# mainboard_interface_v1_2.net
KiCad netlist of a schematic drawn in Altium Designer
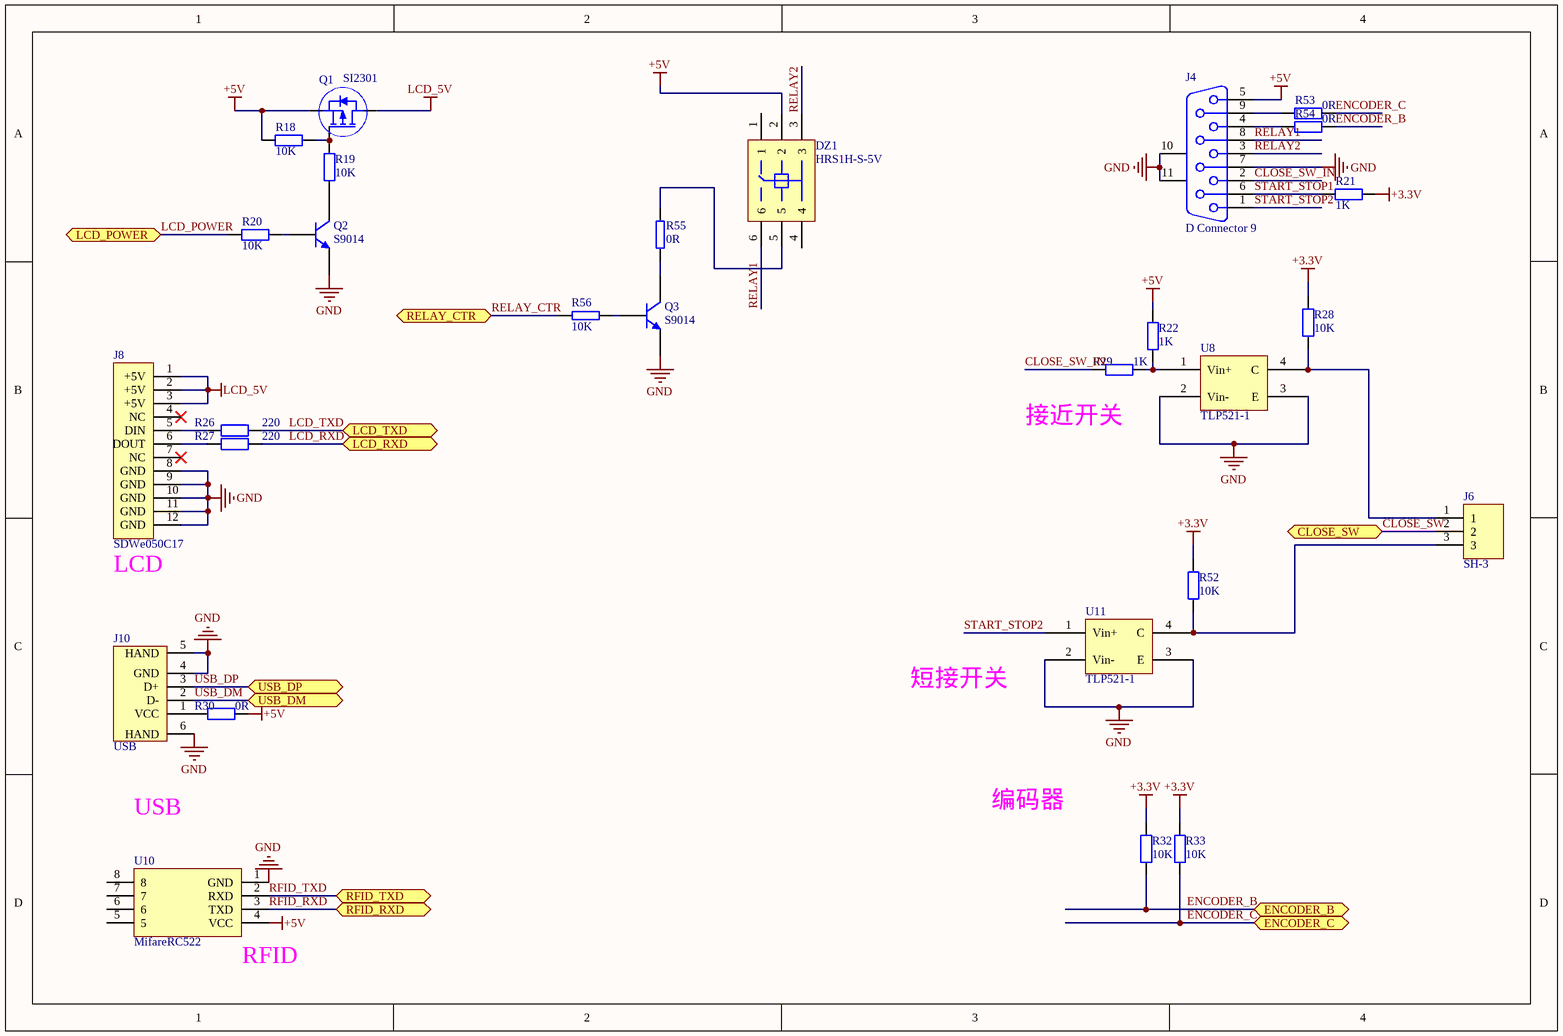
[diagram p0: mainboard_interface.v1.2.SchDoc]

(export (version "E")
  (design (tool "Eeschema 10.0.6"))
  (components
    (comp (ref "DZ1") (value "HRS1H-S-5V") (libsource (lib "Componet") (part "HRS1H-S-5V")))
    (comp (ref "J4")
      (value "D Connector 9")
      (footprint "DSUB1.385-2H9")
      (description "Receptacle Assembly, 9 Position, Right Angle")
      (fields (field (name "PUBLISHER") "Altium Limited"))
      (libsource (lib "Miscellaneous Connectors") (part "D Connector 9"))
    )
    (comp (ref "J6") (value "SH-3") (footprint "J2.54-3") (libsource (lib "Connector") (part "SH-3")))
    (comp (ref "J8")
      (value "SDWe050C17")
      (footprint "FCC1.0-10")
      (libsource (lib "Connector") (part "SH-12"))
    )
    (comp (ref "J10") (value "USB") (footprint "USB_FEMALE_A") (libsource (lib "Connector") (part "USB")))
    (comp (ref "Q1") (value "SI2301") (footprint "MOS-N_SOT-23") (libsource (lib "*") (part "MOS-P_SOT-23")))
    (comp (ref "Q2") (value "S9014") (footprint "901X_SOT-23") (libsource (lib "Componet") (part "NPN")))
    (comp (ref "Q3") (value "S9014") (footprint "901X_SOT-23") (libsource (lib "Componet") (part "NPN")))
    (comp (ref "R18")
      (value "10K")
      (footprint "0805")
      (description "Resistor")
      (fields (field (name "PUBLISHER") "Altium Limited"))
      (libsource (lib "TIAN's Schlib") (part "Res2"))
    )
    (comp (ref "R19")
      (value "10K")
      (footprint "0805")
      (description "Resistor")
      (fields (field (name "PUBLISHER") "Altium Limited"))
      (libsource (lib "") (part "Res2_3"))
    )
    (comp (ref "R20")
      (value "10K")
      (footprint "0805")
      (description "Resistor")
      (fields (field (name "PUBLISHER") "Altium Limited"))
      (libsource (lib "TIAN's Schlib") (part "Res2"))
    )
    (comp (ref "R21")
      (value "1K")
      (footprint "0805")
      (description "Resistor")
      (fields (field (name "PUBLISHER") "Altium Limited"))
      (libsource (lib "TIAN's Schlib") (part "Res2"))
    )
    (comp (ref "R22")
      (value "1K")
      (footprint "0805")
      (description "Resistor")
      (fields (field (name "PUBLISHER") "Altium Limited"))
      (libsource (lib "") (part "Res2_2"))
    )
    (comp (ref "R26")
      (value "220")
      (footprint "0805")
      (description "Resistor")
      (fields (field (name "PUBLISHER") "Altium Limited"))
      (libsource (lib "TIAN's Schlib") (part "Res2"))
    )
    (comp (ref "R27")
      (value "220")
      (footprint "0805")
      (description "Resistor")
      (fields (field (name "PUBLISHER") "Altium Limited"))
      (libsource (lib "TIAN's Schlib") (part "Res2"))
    )
    (comp (ref "R28")
      (value "10K")
      (footprint "0805")
      (description "Resistor")
      (fields (field (name "PUBLISHER") "Altium Limited"))
      (libsource (lib "") (part "Res2_2"))
    )
    (comp (ref "R29")
      (value "1K")
      (footprint "0805")
      (description "Resistor")
      (fields (field (name "PUBLISHER") "Altium Limited"))
      (libsource (lib "") (part "Res2_1"))
    )
    (comp (ref "R30")
      (value "0R")
      (footprint "0805")
      (description "Resistor")
      (fields (field (name "PUBLISHER") "Altium Limited"))
      (libsource (lib "") (part "Res2_1"))
    )
    (comp (ref "R32")
      (value "10K")
      (footprint "0805")
      (description "Resistor")
      (fields (field (name "PUBLISHER") "Altium Limited"))
      (libsource (lib "") (part "Res2_2"))
    )
    (comp (ref "R33")
      (value "10K")
      (footprint "0805")
      (description "Resistor")
      (fields (field (name "PUBLISHER") "Altium Limited"))
      (libsource (lib "") (part "Res2_2"))
    )
    (comp (ref "R52")
      (value "10K")
      (footprint "0805")
      (description "Resistor")
      (fields (field (name "PUBLISHER") "Altium Limited"))
      (libsource (lib "") (part "Res2_2"))
    )
    (comp (ref "R53")
      (value "0R")
      (footprint "0805")
      (description "Resistor")
      (fields (field (name "PUBLISHER") "Altium Limited"))
      (libsource (lib "TIAN's Schlib") (part "Res2"))
    )
    (comp (ref "R54")
      (value "0R")
      (footprint "0805")
      (description "Resistor")
      (fields (field (name "PUBLISHER") "Altium Limited"))
      (libsource (lib "TIAN's Schlib") (part "Res2"))
    )
    (comp (ref "R55")
      (value "0R")
      (footprint "0805")
      (description "电阻")
      (libsource (lib "Component") (part "RES"))
    )
    (comp (ref "R56")
      (value "10K")
      (footprint "0805")
      (description "电阻")
      (libsource (lib "Component") (part "RES"))
    )
    (comp (ref "U8") (value "TLP521-1") (footprint "TLP521-1") (libsource (lib "Chip") (part "TLP521-1")))
    (comp (ref "U10")
      (value "MifareRC522")
      (footprint "MifareRC522")
      (libsource (lib "Componet") (part "MifareRC522"))
    )
    (comp (ref "U11") (value "TLP521-1") (footprint "TLP521-1") (libsource (lib "Chip") (part "TLP521-1")))
  )
  (nets
    (net (code "1") (name "+3.3V") (class "Default")
      (node (ref "R21") (pin "2") (pinfunction "2_2") (pintype "passive"))
      (node (ref "R28") (pin "1") (pinfunction "1_1") (pintype "passive"))
      (node (ref "R32") (pin "1") (pinfunction "1_1") (pintype "passive"))
      (node (ref "R33") (pin "1") (pinfunction "1_1") (pintype "passive"))
      (node (ref "R52") (pin "1") (pinfunction "1_1") (pintype "passive"))
    )
    (net (code "2") (name "+5V") (class "Default")
      (node (ref "DZ1") (pin "2") (pinfunction "2_2") (pintype "passive"))
      (node (ref "J4") (pin "5") (pinfunction "5_5") (pintype "passive"))
      (node (ref "Q1") (pin "S") (pinfunction "S_S") (pintype "passive"))
      (node (ref "R18") (pin "1") (pinfunction "1_1") (pintype "passive"))
      (node (ref "R22") (pin "1") (pinfunction "1_1") (pintype "passive"))
      (node (ref "R30") (pin "1") (pinfunction "1_1") (pintype "passive"))
      (node (ref "U10") (pin "4") (pinfunction "VCC_4") (pintype "passive"))
    )
    (net (code "3") (name "/CLOSE_SW") (class "Default")
      (node (ref "J6") (pin "2") (pinfunction "2_2") (pintype "passive"))
    )
    (net (code "4") (name "/CLOSE_SW_IN") (class "Default")
      (node (ref "J4") (pin "2") (pinfunction "2_2") (pintype "passive"))
      (node (ref "R29") (pin "2") (pinfunction "2_2") (pintype "passive"))
    )
    (net (code "5") (name "/ENCODER_B") (class "Default")
      (node (ref "R32") (pin "2") (pinfunction "2_2") (pintype "passive"))
      (node (ref "R54") (pin "2") (pinfunction "2_2") (pintype "passive"))
    )
    (net (code "6") (name "/ENCODER_C") (class "Default")
      (node (ref "R33") (pin "2") (pinfunction "2_2") (pintype "passive"))
      (node (ref "R53") (pin "2") (pinfunction "2_2") (pintype "passive"))
    )
    (net (code "7") (name "/LCD_POWER") (class "Default")
      (node (ref "R20") (pin "1") (pinfunction "1_1") (pintype "passive"))
    )
    (net (code "8") (name "/LCD_RXD") (class "Default")
      (node (ref "R27") (pin "2") (pinfunction "2_2") (pintype "passive"))
    )
    (net (code "9") (name "/LCD_TXD") (class "Default")
      (node (ref "R26") (pin "2") (pinfunction "2_2") (pintype "passive"))
    )
    (net (code "10") (name "/RELAY1") (class "Default")
      (node (ref "DZ1") (pin "6") (pinfunction "6_6") (pintype "passive"))
      (node (ref "J4") (pin "8") (pinfunction "8_8") (pintype "passive"))
    )
    (net (code "11") (name "/RELAY2") (class "Default")
      (node (ref "DZ1") (pin "3") (pinfunction "3_3") (pintype "passive"))
      (node (ref "J4") (pin "3") (pinfunction "3_3") (pintype "passive"))
    )
    (net (code "12") (name "/RELAY_CTR") (class "Default")
      (node (ref "R56") (pin "2") (pinfunction "2_2") (pintype "passive"))
    )
    (net (code "13") (name "/RFID_RXD") (class "Default")
      (node (ref "U10") (pin "3") (pinfunction "TXD_3") (pintype "passive"))
    )
    (net (code "14") (name "/RFID_TXD") (class "Default")
      (node (ref "U10") (pin "2") (pinfunction "RXD_2") (pintype "passive"))
    )
    (net (code "15") (name "/START_STOP1") (class "Default")
      (node (ref "J4") (pin "6") (pinfunction "6_6") (pintype "passive"))
      (node (ref "R21") (pin "1") (pinfunction "1_1") (pintype "passive"))
    )
    (net (code "16") (name "/START_STOP2") (class "Default")
      (node (ref "J4") (pin "1") (pinfunction "1_1") (pintype "passive"))
      (node (ref "U11") (pin "1") (pinfunction "Vin+_1") (pintype "passive"))
    )
    (net (code "17") (name "/USB_DM") (class "Default")
      (node (ref "J10") (pin "2") (pinfunction "D-_2") (pintype "passive"))
    )
    (net (code "18") (name "/USB_DP") (class "Default")
      (node (ref "J10") (pin "3") (pinfunction "D+_3") (pintype "passive"))
    )
    (net (code "19") (name "GND") (class "Default")
      (node (ref "J10") (pin "4") (pinfunction "GND_4") (pintype "passive"))
      (node (ref "J10") (pin "5") (pinfunction "HAND_5") (pintype "passive"))
      (node (ref "J10") (pin "6") (pinfunction "HAND_6") (pintype "passive"))
      (node (ref "J4") (pin "10") (pinfunction "MH1_10") (pintype "passive"))
      (node (ref "J4") (pin "11") (pinfunction "MH2_11") (pintype "passive"))
      (node (ref "J4") (pin "7") (pinfunction "7_7") (pintype "passive"))
      (node (ref "J8") (pin "10") (pinfunction "GND_10") (pintype "passive"))
      (node (ref "J8") (pin "11") (pinfunction "GND_11") (pintype "passive"))
      (node (ref "J8") (pin "12") (pinfunction "GND_12") (pintype "passive"))
      (node (ref "J8") (pin "8") (pinfunction "GND_8") (pintype "passive"))
      (node (ref "J8") (pin "9") (pinfunction "GND_9") (pintype "passive"))
      (node (ref "Q2") (pin "3") (pinfunction "E_3") (pintype "passive"))
      (node (ref "Q3") (pin "3") (pinfunction "E_3") (pintype "passive"))
      (node (ref "U10") (pin "1") (pinfunction "GND_1") (pintype "passive"))
      (node (ref "U11") (pin "2") (pinfunction "Vin-_2") (pintype "passive"))
      (node (ref "U11") (pin "3") (pinfunction "E_3") (pintype "passive"))
      (node (ref "U8") (pin "2") (pinfunction "Vin-_2") (pintype "passive"))
      (node (ref "U8") (pin "3") (pinfunction "E_3") (pintype "passive"))
    )
    (net (code "20") (name "LCD_5V") (class "Default")
      (node (ref "J8") (pin "1") (pinfunction "+5V_1") (pintype "passive"))
      (node (ref "J8") (pin "2") (pinfunction "+5V_2") (pintype "passive"))
      (node (ref "J8") (pin "3") (pinfunction "+5V_3") (pintype "passive"))
      (node (ref "Q1") (pin "D") (pinfunction "D_D") (pintype "passive"))
    )
    (net (code "21") (name "Net-(DZ1-Pad5)") (class "Default")
      (node (ref "DZ1") (pin "5") (pinfunction "5_5") (pintype "passive"))
      (node (ref "R55") (pin "2") (pinfunction "2_2") (pintype "passive"))
    )
    (net (code "22") (name "Net-(J4-Pad4)") (class "Default")
      (node (ref "J4") (pin "4") (pinfunction "4_4") (pintype "passive"))
      (node (ref "R54") (pin "1") (pinfunction "1_1") (pintype "passive"))
    )
    (net (code "23") (name "Net-(J4-Pad9)") (class "Default")
      (node (ref "J4") (pin "9") (pinfunction "9_9") (pintype "passive"))
      (node (ref "R53") (pin "1") (pinfunction "1_1") (pintype "passive"))
    )
    (net (code "24") (name "Net-(J8-DIN)") (class "Default")
      (node (ref "J8") (pin "5") (pinfunction "DIN_5") (pintype "passive"))
      (node (ref "R26") (pin "1") (pinfunction "1_1") (pintype "passive"))
    )
    (net (code "25") (name "Net-(J8-DOUT)") (class "Default")
      (node (ref "J8") (pin "6") (pinfunction "DOUT_6") (pintype "passive"))
      (node (ref "R27") (pin "1") (pinfunction "1_1") (pintype "passive"))
    )
    (net (code "26") (name "Net-(J10-VCC)") (class "Default")
      (node (ref "J10") (pin "1") (pinfunction "VCC_1") (pintype "passive"))
      (node (ref "R30") (pin "2") (pinfunction "2_2") (pintype "passive"))
    )
    (net (code "27") (name "Net-(Q1-PadG)") (class "Default")
      (node (ref "Q1") (pin "G") (pinfunction "G_G") (pintype "passive"))
      (node (ref "R18") (pin "2") (pinfunction "2_2") (pintype "passive"))
      (node (ref "R19") (pin "2") (pinfunction "2_2") (pintype "passive"))
    )
    (net (code "28") (name "Net-(Q2-B)") (class "Default")
      (node (ref "Q2") (pin "2") (pinfunction "B_2") (pintype "passive"))
      (node (ref "R20") (pin "2") (pinfunction "2_2") (pintype "passive"))
    )
    (net (code "29") (name "Net-(Q2-C)") (class "Default")
      (node (ref "Q2") (pin "1") (pinfunction "C_1") (pintype "passive"))
      (node (ref "R19") (pin "1") (pinfunction "1_1") (pintype "passive"))
    )
    (net (code "30") (name "Net-(Q3-B)") (class "Default")
      (node (ref "Q3") (pin "2") (pinfunction "B_2") (pintype "passive"))
      (node (ref "R56") (pin "1") (pinfunction "1_1") (pintype "passive"))
    )
    (net (code "31") (name "Net-(Q3-C)") (class "Default")
      (node (ref "Q3") (pin "1") (pinfunction "C_1") (pintype "passive"))
      (node (ref "R55") (pin "1") (pinfunction "1_1") (pintype "passive"))
    )
    (net (code "32") (name "Net-(U8-C)") (class "Default")
      (node (ref "J6") (pin "1") (pinfunction "1_1") (pintype "passive"))
      (node (ref "R28") (pin "2") (pinfunction "2_2") (pintype "passive"))
      (node (ref "U8") (pin "4") (pinfunction "C_4") (pintype "passive"))
    )
    (net (code "33") (name "Net-(U8-Vin+)") (class "Default")
      (node (ref "R22") (pin "2") (pinfunction "2_2") (pintype "passive"))
      (node (ref "R29") (pin "1") (pinfunction "1_1") (pintype "passive"))
      (node (ref "U8") (pin "1") (pinfunction "Vin+_1") (pintype "passive"))
    )
    (net (code "34") (name "Net-(U11-C)") (class "Default")
      (node (ref "J6") (pin "3") (pinfunction "3_3") (pintype "passive"))
      (node (ref "R52") (pin "2") (pinfunction "2_2") (pintype "passive"))
      (node (ref "U11") (pin "4") (pinfunction "C_4") (pintype "passive"))
    )
    (net (code "35") (name "unconnected-(DZ1-Pad1)") (class "Default")
      (node (ref "DZ1") (pin "1") (pinfunction "1_1") (pintype "passive"))
    )
    (net (code "36") (name "unconnected-(DZ1-Pad4)") (class "Default")
      (node (ref "DZ1") (pin "4") (pinfunction "4_4") (pintype "passive"))
    )
    (net (code "37") (name "unconnected-(J8-NC-Pad4)") (class "Default")
      (node (ref "J8") (pin "4") (pinfunction "NC_4") (pintype "passive+no_connect"))
    )
    (net (code "38") (name "unconnected-(J8-NC-Pad7)") (class "Default")
      (node (ref "J8") (pin "7") (pinfunction "NC_7") (pintype "passive+no_connect"))
    )
    (net (code "39") (name "unconnected-(U10-Pad5)") (class "Default")
      (node (ref "U10") (pin "5") (pinfunction "5_5") (pintype "passive"))
    )
    (net (code "40") (name "unconnected-(U10-Pad6)") (class "Default")
      (node (ref "U10") (pin "6") (pinfunction "6_6") (pintype "passive"))
    )
    (net (code "41") (name "unconnected-(U10-Pad7)") (class "Default")
      (node (ref "U10") (pin "7") (pinfunction "7_7") (pintype "passive"))
    )
    (net (code "42") (name "unconnected-(U10-Pad8)") (class "Default")
      (node (ref "U10") (pin "8") (pinfunction "8_8") (pintype "passive"))
    )
  )
)
